# documentation_schema.net
KiCad netlist of a schematic drawn in EAGLE
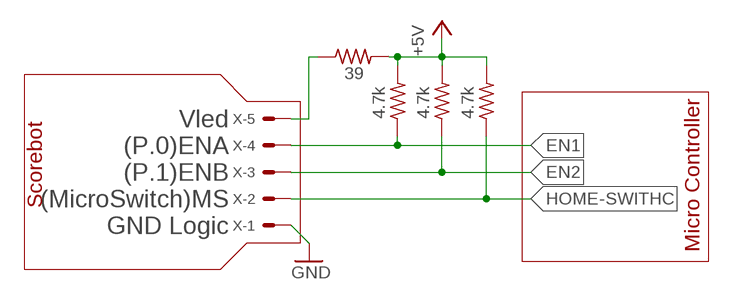
[diagram p0: schematic, sheet 1]

(export (version "E")
  (design (tool "Eeschema 10.0.6"))
  (components
    (comp (ref "R1")
      (value "39")
      (footprint "eagle-import:0204_5")
      (libsource (lib "eagle-import") (part "R-US_0204/5"))
    )
    (comp (ref "R2")
      (value "4.7k")
      (footprint "eagle-import:0204_5")
      (libsource (lib "eagle-import") (part "R-US_0204/5"))
    )
    (comp (ref "R3")
      (value "4.7k")
      (footprint "eagle-import:0204_5")
      (libsource (lib "eagle-import") (part "R-US_0204/5"))
    )
    (comp (ref "R4")
      (value "4.7k")
      (footprint "eagle-import:0204_5")
      (libsource (lib "eagle-import") (part "R-US_0204/5"))
    )
    (comp (ref "X")
      (value "22-23-2051")
      (footprint "eagle-import:22-23-2051")
      (fields (field (name "MF") "MOLEX"))
      (libsource (lib "eagle-import") (part "22-23-2051"))
    )
  )
  (nets
    (net (code "1") (name "+5V") (class "Default")
      (node (ref "R1") (pin "2") (pinfunction "2_2") (pintype "passive"))
      (node (ref "R2") (pin "2") (pinfunction "2_2") (pintype "passive"))
      (node (ref "R3") (pin "2") (pinfunction "2_2") (pintype "passive"))
      (node (ref "R4") (pin "2") (pinfunction "2_2") (pintype "passive"))
    )
    (net (code "2") (name "EN1") (class "Default")
      (node (ref "R4") (pin "1") (pinfunction "1_1") (pintype "passive"))
      (node (ref "X") (pin "4") (pinfunction "S_4") (pintype "passive"))
    )
    (net (code "3") (name "EN2") (class "Default")
      (node (ref "R3") (pin "1") (pinfunction "1_1") (pintype "passive"))
      (node (ref "X") (pin "3") (pinfunction "S_3") (pintype "passive"))
    )
    (net (code "4") (name "GND") (class "Default")
      (node (ref "X") (pin "1") (pinfunction "S_1") (pintype "passive"))
    )
    (net (code "5") (name "HOME-SWITHC") (class "Default")
      (node (ref "R2") (pin "1") (pinfunction "1_1") (pintype "passive"))
      (node (ref "X") (pin "2") (pinfunction "S_2") (pintype "passive"))
    )
    (net (code "6") (name "Net-(XE-S)") (class "Default")
      (node (ref "R1") (pin "1") (pinfunction "1_1") (pintype "passive"))
      (node (ref "X") (pin "5") (pinfunction "S_5") (pintype "passive"))
    )
  )
)
